# ExtraCore_2.net
KiCad netlist of a schematic drawn in EAGLE
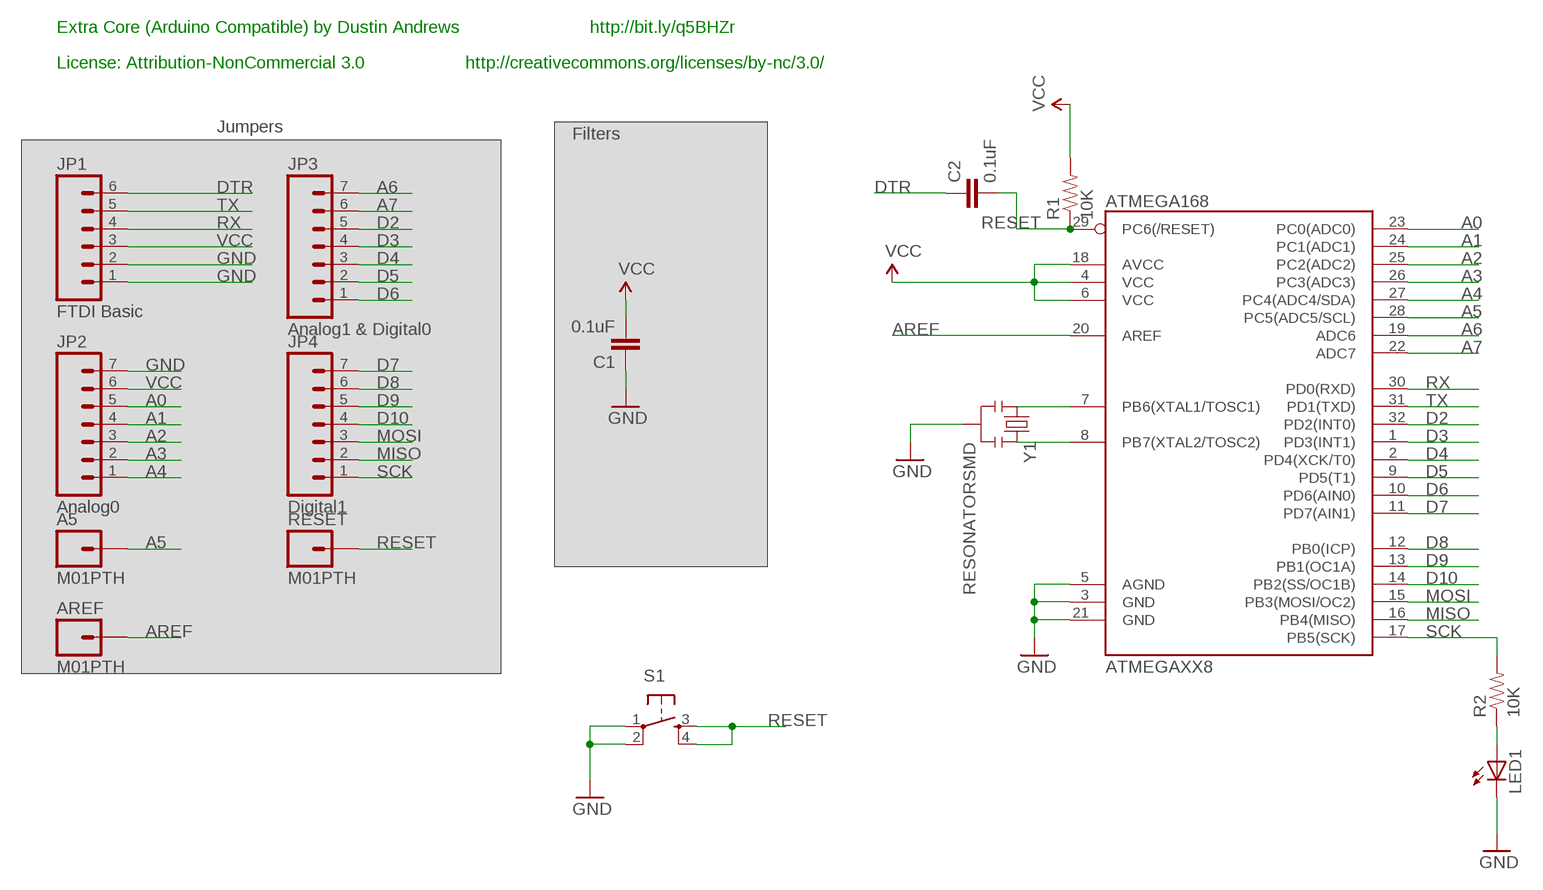
[diagram p0: schematic, sheet 1]

(export (version "E")
  (design (tool "Eeschema 10.0.6"))
  (components
    (comp (ref "A5")
      (value "M01PTH")
      (footprint "eagle-import:1X01")
      (libsource (lib "eagle-import") (part "M01PTH"))
    )
    (comp (ref "AREF")
      (value "M01PTH")
      (footprint "eagle-import:1X01")
      (libsource (lib "eagle-import") (part "M01PTH"))
    )
    (comp (ref "ATMEGAXX8")
      (value "ATMEGA168")
      (footprint "eagle-import:TQFP32-08")
      (libsource (lib "eagle-import") (part "ATMEGA168"))
    )
    (comp (ref "C1")
      (value "0.1uF")
      (footprint "eagle-import:0805")
      (libsource (lib "eagle-import") (part "CAP0805"))
    )
    (comp (ref "C2")
      (value "0.1uF")
      (footprint "eagle-import:0805")
      (libsource (lib "eagle-import") (part "CAP0805"))
    )
    (comp (ref "JP1")
      (value "FTDI Basic")
      (footprint "eagle-import:1X06")
      (libsource (lib "eagle-import") (part "M06SIP"))
    )
    (comp (ref "JP2")
      (value "Analog0")
      (footprint "eagle-import:1X07")
      (libsource (lib "eagle-import") (part "M07"))
    )
    (comp (ref "JP3")
      (value "Analog1 & Digital0")
      (footprint "eagle-import:1X07")
      (libsource (lib "eagle-import") (part "M07"))
    )
    (comp (ref "JP4")
      (value "Digital1")
      (footprint "eagle-import:1X07")
      (libsource (lib "eagle-import") (part "M07"))
    )
    (comp (ref "LED1")
      (value "LEDCHIP-LED0805")
      (footprint "eagle-import:CHIP-LED0805")
      (libsource (lib "eagle-import") (part "LEDCHIP-LED0805"))
    )
    (comp (ref "R1")
      (value "10K")
      (footprint "eagle-import:0805")
      (libsource (lib "eagle-import") (part "RESISTOR0805-RES"))
    )
    (comp (ref "R2")
      (value "10K")
      (footprint "eagle-import:0805")
      (libsource (lib "eagle-import") (part "RESISTOR0805-RES"))
    )
    (comp (ref "RESET")
      (value "M01PTH")
      (footprint "eagle-import:1X01")
      (libsource (lib "eagle-import") (part "M01PTH"))
    )
    (comp (ref "S1")
      (value "TAC_SWITCHSMD")
      (footprint "eagle-import:TACTILE_SWITCH_SMD")
      (libsource (lib "eagle-import") (part "TAC_SWITCHSMD"))
    )
    (comp (ref "Y1")
      (value "RESONATORSMD")
      (footprint "eagle-import:RESONATOR-SMD")
      (libsource (lib "eagle-import") (part "RESONATORSMD"))
    )
  )
  (nets
    (net (code "1") (name "/A0") (class "Default")
      (node (ref "ATMEGAXX8") (pin "23") (pinfunction "PC0(ADC0)_23") (pintype "bidirectional"))
      (node (ref "JP2") (pin "5") (pinfunction "5_5") (pintype "passive"))
    )
    (net (code "2") (name "/A1") (class "Default")
      (node (ref "ATMEGAXX8") (pin "24") (pinfunction "PC1(ADC1)_24") (pintype "bidirectional"))
      (node (ref "JP2") (pin "4") (pinfunction "4_4") (pintype "passive"))
    )
    (net (code "3") (name "/A2") (class "Default")
      (node (ref "ATMEGAXX8") (pin "25") (pinfunction "PC2(ADC2)_25") (pintype "bidirectional"))
      (node (ref "JP2") (pin "3") (pinfunction "3_3") (pintype "passive"))
    )
    (net (code "4") (name "/A3") (class "Default")
      (node (ref "ATMEGAXX8") (pin "26") (pinfunction "PC3(ADC3)_26") (pintype "bidirectional"))
      (node (ref "JP2") (pin "2") (pinfunction "2_2") (pintype "passive"))
    )
    (net (code "5") (name "/A4") (class "Default")
      (node (ref "ATMEGAXX8") (pin "27") (pinfunction "PC4(ADC4/SDA)_27") (pintype "bidirectional"))
      (node (ref "JP2") (pin "1") (pinfunction "1_1") (pintype "passive"))
    )
    (net (code "6") (name "/A5") (class "Default")
      (node (ref "A5") (pin "1") (pinfunction "1_1") (pintype "passive"))
      (node (ref "ATMEGAXX8") (pin "28") (pinfunction "PC5(ADC5/SCL)_28") (pintype "bidirectional"))
    )
    (net (code "7") (name "/A6") (class "Default")
      (node (ref "ATMEGAXX8") (pin "19") (pinfunction "ADC6_19") (pintype "bidirectional"))
      (node (ref "JP3") (pin "7") (pinfunction "7_7") (pintype "passive"))
    )
    (net (code "8") (name "/A7") (class "Default")
      (node (ref "ATMEGAXX8") (pin "22") (pinfunction "ADC7_22") (pintype "bidirectional"))
      (node (ref "JP3") (pin "6") (pinfunction "6_6") (pintype "passive"))
    )
    (net (code "9") (name "/AREF") (class "Default")
      (node (ref "AREF") (pin "1") (pinfunction "1_1") (pintype "passive"))
      (node (ref "ATMEGAXX8") (pin "20") (pinfunction "AREF_20") (pintype "bidirectional"))
    )
    (net (code "10") (name "/D2") (class "Default")
      (node (ref "ATMEGAXX8") (pin "32") (pinfunction "PD2(INT0)_32") (pintype "bidirectional"))
      (node (ref "JP3") (pin "5") (pinfunction "5_5") (pintype "passive"))
    )
    (net (code "11") (name "/D3") (class "Default")
      (node (ref "ATMEGAXX8") (pin "1") (pinfunction "PD3(INT1)_1") (pintype "bidirectional"))
      (node (ref "JP3") (pin "4") (pinfunction "4_4") (pintype "passive"))
    )
    (net (code "12") (name "/D4") (class "Default")
      (node (ref "ATMEGAXX8") (pin "2") (pinfunction "PD4(XCK/T0)_2") (pintype "bidirectional"))
      (node (ref "JP3") (pin "3") (pinfunction "3_3") (pintype "passive"))
    )
    (net (code "13") (name "/D5") (class "Default")
      (node (ref "ATMEGAXX8") (pin "9") (pinfunction "PD5(T1)_9") (pintype "bidirectional"))
      (node (ref "JP3") (pin "2") (pinfunction "2_2") (pintype "passive"))
    )
    (net (code "14") (name "/D6") (class "Default")
      (node (ref "ATMEGAXX8") (pin "10") (pinfunction "PD6(AIN0)_10") (pintype "bidirectional"))
      (node (ref "JP3") (pin "1") (pinfunction "1_1") (pintype "passive"))
    )
    (net (code "15") (name "/D7") (class "Default")
      (node (ref "ATMEGAXX8") (pin "11") (pinfunction "PD7(AIN1)_11") (pintype "bidirectional"))
      (node (ref "JP4") (pin "7") (pinfunction "7_7") (pintype "passive"))
    )
    (net (code "16") (name "/D8") (class "Default")
      (node (ref "ATMEGAXX8") (pin "12") (pinfunction "PB0(ICP)_12") (pintype "bidirectional"))
      (node (ref "JP4") (pin "6") (pinfunction "6_6") (pintype "passive"))
    )
    (net (code "17") (name "/D9") (class "Default")
      (node (ref "ATMEGAXX8") (pin "13") (pinfunction "PB1(OC1A)_13") (pintype "bidirectional"))
      (node (ref "JP4") (pin "5") (pinfunction "5_5") (pintype "passive"))
    )
    (net (code "18") (name "/D10") (class "Default")
      (node (ref "ATMEGAXX8") (pin "14") (pinfunction "PB2(SS/OC1B)_14") (pintype "bidirectional"))
      (node (ref "JP4") (pin "4") (pinfunction "4_4") (pintype "passive"))
    )
    (net (code "19") (name "/DTR") (class "Default")
      (node (ref "C2") (pin "1") (pinfunction "1_1") (pintype "passive"))
      (node (ref "JP1") (pin "6") (pinfunction "6_6") (pintype "passive"))
    )
    (net (code "20") (name "/MISO") (class "Default")
      (node (ref "ATMEGAXX8") (pin "16") (pinfunction "PB4(MISO)_16") (pintype "bidirectional"))
      (node (ref "JP4") (pin "2") (pinfunction "2_2") (pintype "passive"))
    )
    (net (code "21") (name "/MOSI") (class "Default")
      (node (ref "ATMEGAXX8") (pin "15") (pinfunction "PB3(MOSI/OC2)_15") (pintype "bidirectional"))
      (node (ref "JP4") (pin "3") (pinfunction "3_3") (pintype "passive"))
    )
    (net (code "22") (name "/RESET") (class "Default")
      (node (ref "ATMEGAXX8") (pin "29") (pinfunction "PC6(/RESET)_29") (pintype "bidirectional"))
      (node (ref "C2") (pin "2") (pinfunction "2_2") (pintype "passive"))
      (node (ref "R1") (pin "1") (pinfunction "1_1") (pintype "passive"))
      (node (ref "RESET") (pin "1") (pinfunction "1_1") (pintype "passive"))
      (node (ref "S1") (pin "3") (pinfunction "3_3") (pintype "passive"))
      (node (ref "S1") (pin "4") (pinfunction "4_4") (pintype "passive"))
    )
    (net (code "23") (name "/RX") (class "Default")
      (node (ref "ATMEGAXX8") (pin "30") (pinfunction "PD0(RXD)_30") (pintype "bidirectional"))
      (node (ref "JP1") (pin "4") (pinfunction "4_4") (pintype "passive"))
    )
    (net (code "24") (name "/SCK") (class "Default")
      (node (ref "ATMEGAXX8") (pin "17") (pinfunction "PB5(SCK)_17") (pintype "bidirectional"))
      (node (ref "JP4") (pin "1") (pinfunction "1_1") (pintype "passive"))
      (node (ref "R2") (pin "2") (pinfunction "2_2") (pintype "passive"))
    )
    (net (code "25") (name "/TX") (class "Default")
      (node (ref "ATMEGAXX8") (pin "31") (pinfunction "PD1(TXD)_31") (pintype "bidirectional"))
      (node (ref "JP1") (pin "5") (pinfunction "5_5") (pintype "passive"))
    )
    (net (code "26") (name "GND") (class "Default")
      (node (ref "ATMEGAXX8") (pin "21") (pinfunction "GND_21") (pintype "bidirectional"))
      (node (ref "ATMEGAXX8") (pin "3") (pinfunction "GND_3") (pintype "bidirectional"))
      (node (ref "ATMEGAXX8") (pin "5") (pinfunction "AGND_5") (pintype "bidirectional"))
      (node (ref "C1") (pin "1") (pinfunction "1_1") (pintype "passive"))
      (node (ref "JP1") (pin "1") (pinfunction "1_1") (pintype "passive"))
      (node (ref "JP1") (pin "2") (pinfunction "2_2") (pintype "passive"))
      (node (ref "JP2") (pin "7") (pinfunction "7_7") (pintype "passive"))
      (node (ref "LED1") (pin "C") (pinfunction "C_C") (pintype "passive"))
      (node (ref "S1") (pin "1") (pinfunction "1_1") (pintype "passive"))
      (node (ref "S1") (pin "2") (pinfunction "2_2") (pintype "passive"))
      (node (ref "Y1") (pin "2") (pinfunction "2_2") (pintype "passive"))
    )
    (net (code "27") (name "Net-(ATMEGAXX8-PB6(XTAL1{slash}TOSC1))") (class "Default")
      (node (ref "ATMEGAXX8") (pin "7") (pinfunction "PB6(XTAL1/TOSC1)_7") (pintype "bidirectional"))
      (node (ref "Y1") (pin "1") (pinfunction "1_1") (pintype "passive"))
    )
    (net (code "28") (name "Net-(ATMEGAXX8-PB7(XTAL2{slash}TOSC2))") (class "Default")
      (node (ref "ATMEGAXX8") (pin "8") (pinfunction "PB7(XTAL2/TOSC2)_8") (pintype "bidirectional"))
      (node (ref "Y1") (pin "3") (pinfunction "3_3") (pintype "passive"))
    )
    (net (code "29") (name "Net-(LED1-PadA)") (class "Default")
      (node (ref "LED1") (pin "A") (pinfunction "A_A") (pintype "passive"))
      (node (ref "R2") (pin "1") (pinfunction "1_1") (pintype "passive"))
    )
    (net (code "30") (name "VCC") (class "Default")
      (node (ref "ATMEGAXX8") (pin "18") (pinfunction "AVCC_18") (pintype "bidirectional"))
      (node (ref "ATMEGAXX8") (pin "4") (pinfunction "VCC_4") (pintype "bidirectional"))
      (node (ref "ATMEGAXX8") (pin "6") (pinfunction "VCC_6") (pintype "bidirectional"))
      (node (ref "C1") (pin "2") (pinfunction "2_2") (pintype "passive"))
      (node (ref "JP1") (pin "3") (pinfunction "3_3") (pintype "passive"))
      (node (ref "JP2") (pin "6") (pinfunction "6_6") (pintype "passive"))
      (node (ref "R1") (pin "2") (pinfunction "2_2") (pintype "passive"))
    )
  )
)
